# practice_1.net
KiCad netlist of a schematic drawn in EAGLE
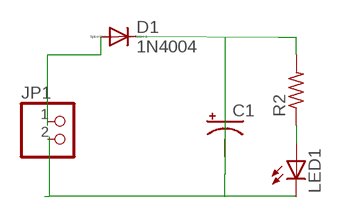
[diagram p0: schematic, sheet 1]

(export (version "E")
  (design (tool "Eeschema 10.0.6"))
  (components
    (comp (ref "C1")
      (value "CPOL-USE3.5-10")
      (footprint "eagle-import:E3,5-10")
      (libsource (lib "eagle-import") (part "CPOL-USE3.5-10"))
    )
    (comp (ref "D1")
      (value "1N4004")
      (footprint "eagle-import:DO41-10")
      (libsource (lib "eagle-import") (part "1N4004"))
    )
    (comp (ref "JP1")
      (value "PINHD-1X2")
      (footprint "eagle-import:1X02")
      (libsource (lib "eagle-import") (part "PINHD-1X2"))
    )
    (comp (ref "LED1")
      (value "LED3MM")
      (footprint "eagle-import:LED3MM")
      (libsource (lib "eagle-import") (part "LED3MM"))
    )
    (comp (ref "R2")
      (value "R-US_0207/10")
      (footprint "eagle-import:0207_10")
      (libsource (lib "eagle-import") (part "R-US_0207/10"))
    )
  )
  (nets
    (net (code "1") (name "Net-(LED1-PadA)") (class "Default")
      (node (ref "LED1") (pin "A") (pinfunction "A_A") (pintype "passive"))
      (node (ref "R2") (pin "1") (pinfunction "1_1") (pintype "passive"))
    )
    (net (code "2") (name "unconnected-(C1-Pad+)") (class "Default")
      (node (ref "C1") (pin "+") (pinfunction "+_+") (pintype "passive"))
    )
    (net (code "3") (name "unconnected-(C1-Pad-)") (class "Default")
      (node (ref "C1") (pin "-") (pinfunction "-_-") (pintype "passive"))
    )
    (net (code "4") (name "unconnected-(D1-PadA)") (class "Default")
      (node (ref "D1") (pin "A") (pinfunction "A_A") (pintype "passive"))
    )
    (net (code "5") (name "unconnected-(D1-PadC)") (class "Default")
      (node (ref "D1") (pin "C") (pinfunction "C_C") (pintype "passive"))
    )
    (net (code "6") (name "unconnected-(JP1-Pad1)") (class "Default")
      (node (ref "JP1") (pin "1") (pinfunction "1_1") (pintype "passive"))
    )
    (net (code "7") (name "unconnected-(JP1-Pad2)") (class "Default")
      (node (ref "JP1") (pin "2") (pinfunction "2_2") (pintype "passive"))
    )
    (net (code "8") (name "unconnected-(LED1-C-PadK)") (class "Default")
      (node (ref "LED1") (pin "K") (pinfunction "C_K") (pintype "passive"))
    )
    (net (code "9") (name "unconnected-(R2-Pad2)") (class "Default")
      (node (ref "R2") (pin "2") (pinfunction "2_2") (pintype "passive"))
    )
  )
)
